# SCH_breakout_board_for_servo_2022-09-03.net
KiCad netlist of a schematic drawn in EasyEDA
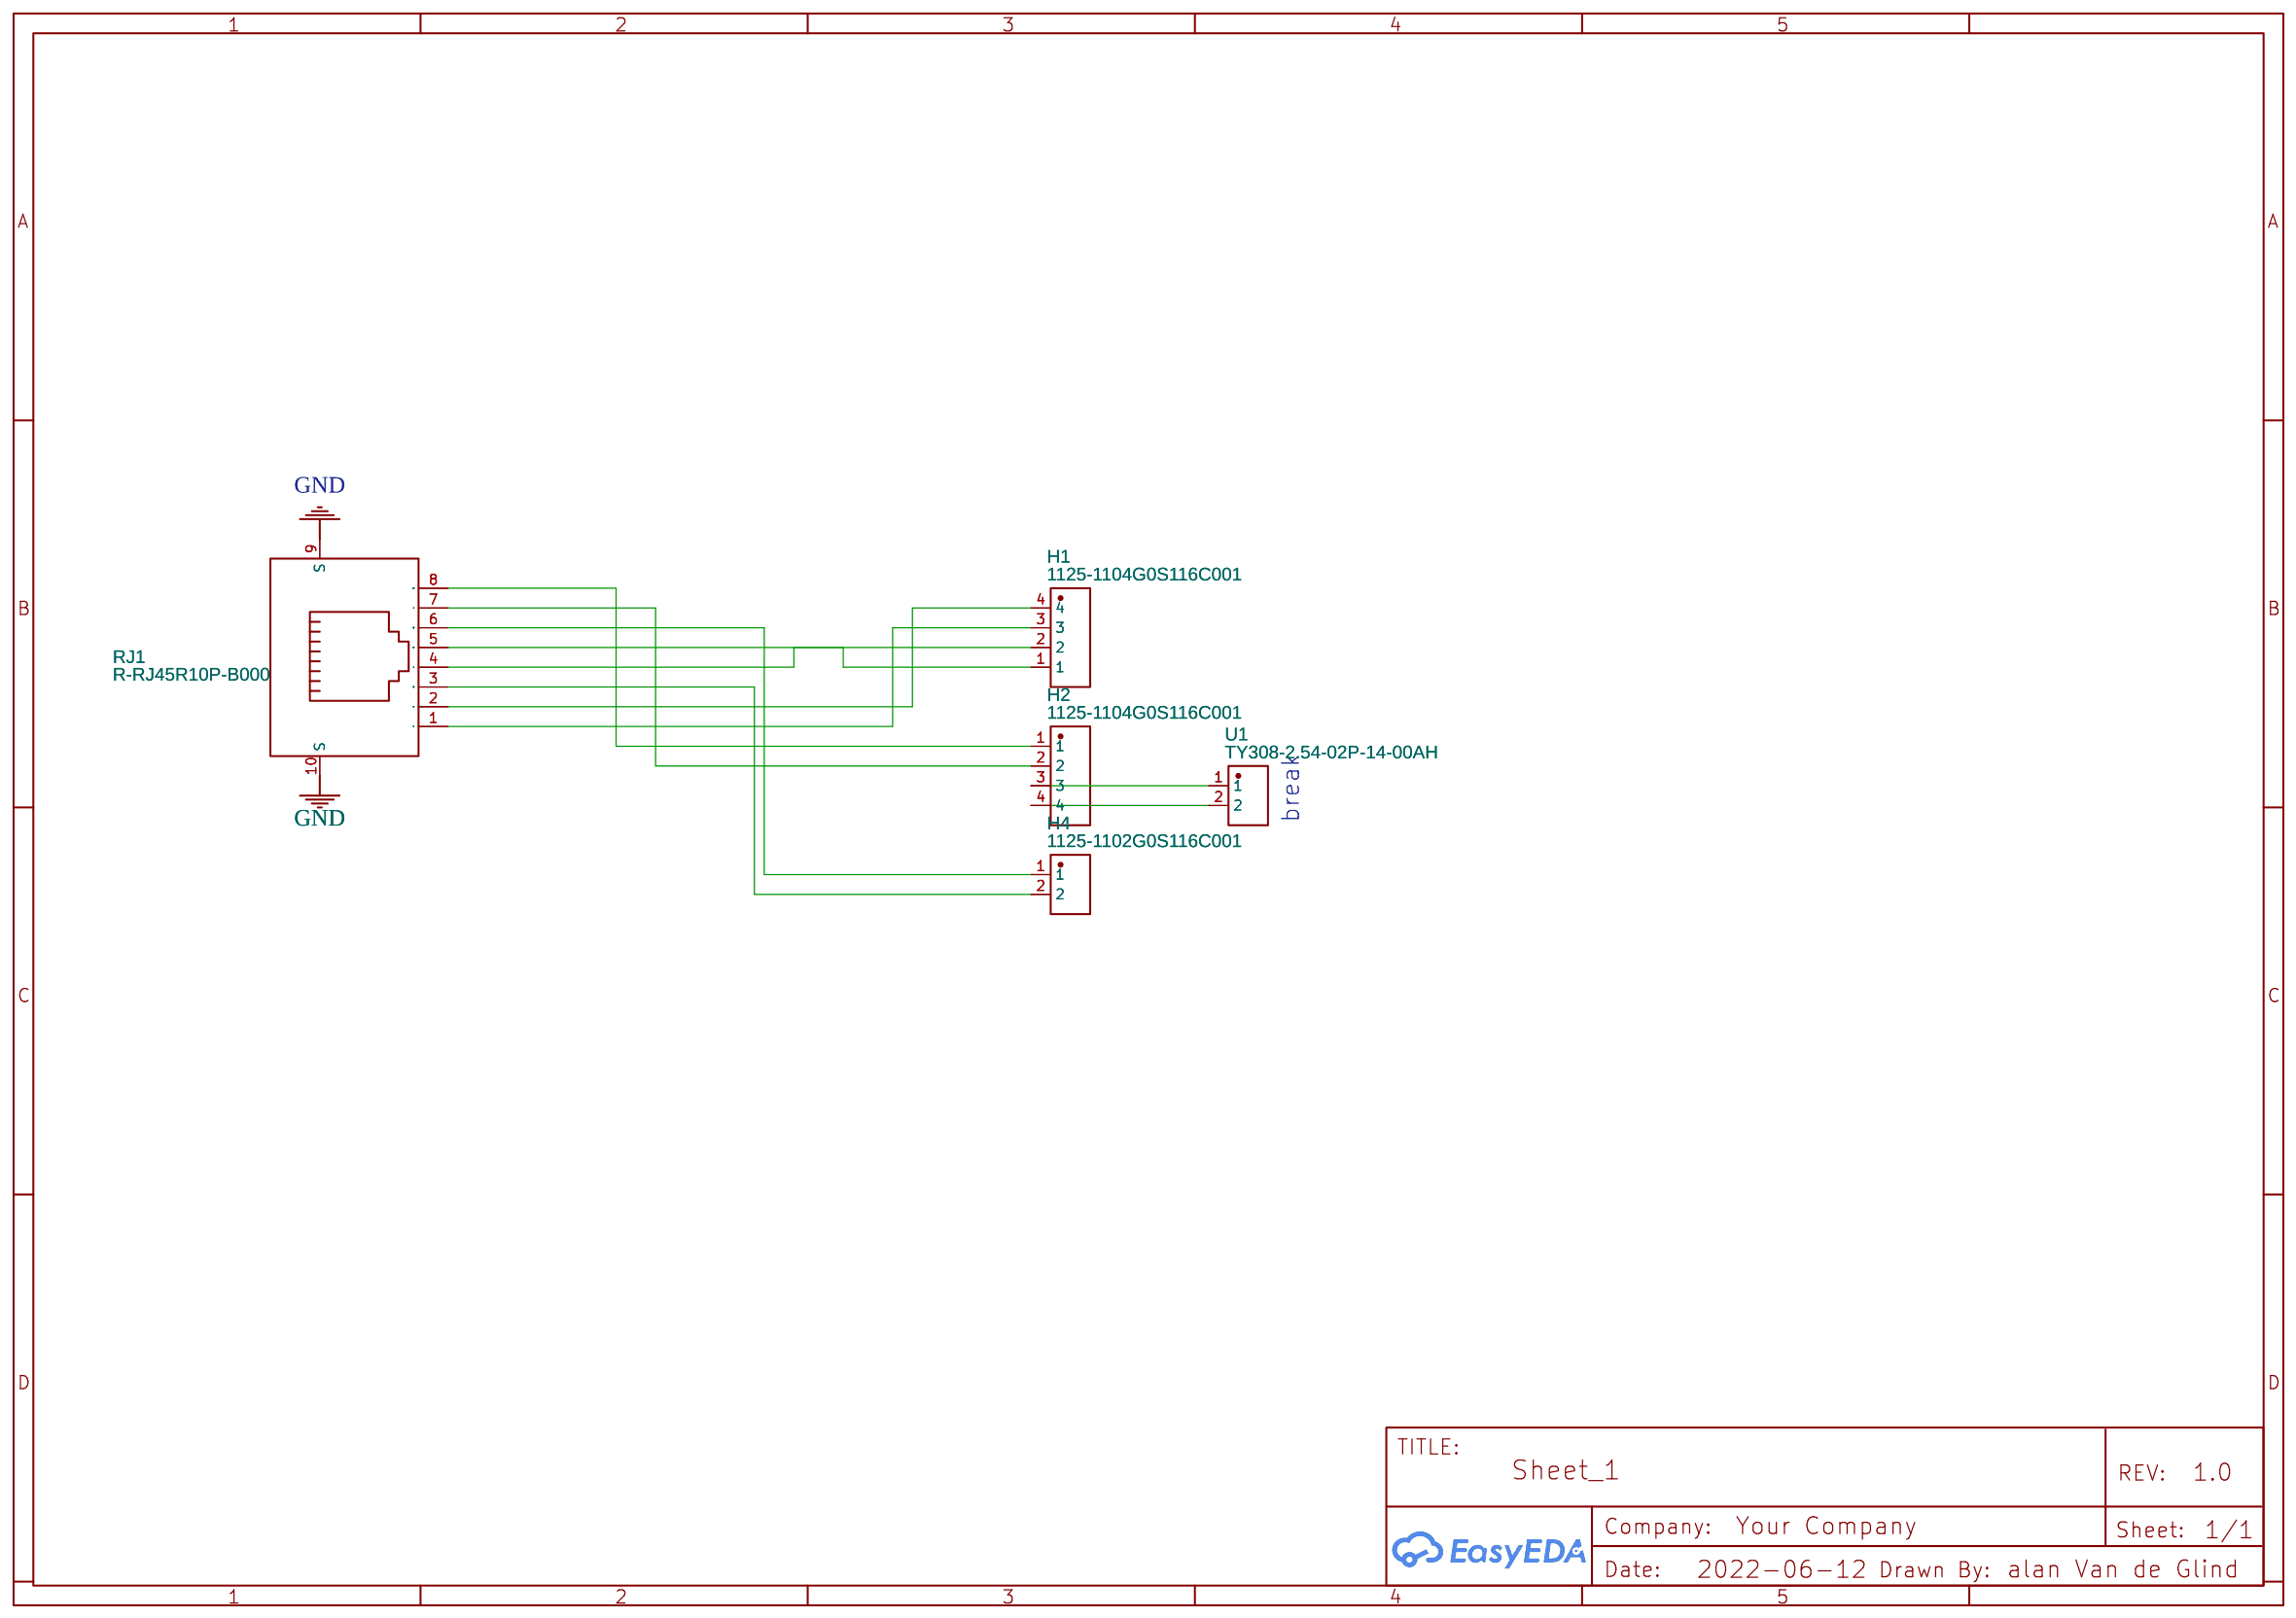
[diagram p0: schematic sheet]

(export (version "E")
  (design (tool "Eeschema 10.0.6"))
  (components
    (comp (ref "H1")
      (value "1125-1104G0S116C001")
      (fields (field (name "BOM_Supplier Part") "C920779"))
      (libsource (lib "") (part "1125-1104G0S116C001_1"))
    )
    (comp (ref "H2")
      (value "1125-1104G0S116C001")
      (fields (field (name "BOM_Supplier Part") "C920779"))
      (libsource (lib "") (part "1125-1104G0S116C001"))
    )
    (comp (ref "H4")
      (value "1125-1102G0S116C001")
      (fields (field (name "BOM_Supplier Part") "C920781"))
      (libsource (lib "") (part "1125-1102G0S116C001"))
    )
    (comp (ref "RJ1")
      (value "R-RJ45R10P-B000")
      (fields (field (name "BOM_Supplier Part") "C386758"))
      (libsource (lib "") (part "R-RJ45R10P-B000"))
    )
    (comp (ref "U1")
      (value "TY308-2.54-02P-14-00AH")
      (fields (field (name "BOM_Supplier Part") "C2840316"))
      (libsource (lib "") (part "TY308-2.54-02P-14-00AH"))
    )
  )
  (nets
    (net (code "1") (name "GND") (class "Default")
      (node (ref "RJ1") (pin "10") (pinfunction "S_10") (pintype "unspecified"))
      (node (ref "RJ1") (pin "9") (pinfunction "S_9") (pintype "unspecified"))
    )
    (net (code "2") (name "Net-(H1-Pad1)") (class "Default")
      (node (ref "H1") (pin "1") (pinfunction "1_1") (pintype "unspecified"))
      (node (ref "RJ1") (pin "5") (pinfunction "5_5") (pintype "unspecified"))
    )
    (net (code "3") (name "Net-(H1-Pad2)") (class "Default")
      (node (ref "H1") (pin "2") (pinfunction "2_2") (pintype "unspecified"))
      (node (ref "RJ1") (pin "4") (pinfunction "4_4") (pintype "unspecified"))
    )
    (net (code "4") (name "Net-(H1-Pad3)") (class "Default")
      (node (ref "H1") (pin "3") (pinfunction "3_3") (pintype "unspecified"))
      (node (ref "RJ1") (pin "1") (pinfunction "1_1") (pintype "unspecified"))
    )
    (net (code "5") (name "Net-(H1-Pad4)") (class "Default")
      (node (ref "H1") (pin "4") (pinfunction "4_4") (pintype "unspecified"))
      (node (ref "RJ1") (pin "2") (pinfunction "2_2") (pintype "unspecified"))
    )
    (net (code "6") (name "Net-(H2-Pad1)") (class "Default")
      (node (ref "H2") (pin "1") (pinfunction "1_1") (pintype "unspecified"))
      (node (ref "RJ1") (pin "8") (pinfunction "8_8") (pintype "unspecified"))
    )
    (net (code "7") (name "Net-(H2-Pad2)") (class "Default")
      (node (ref "H2") (pin "2") (pinfunction "2_2") (pintype "unspecified"))
      (node (ref "RJ1") (pin "7") (pinfunction "7_7") (pintype "unspecified"))
    )
    (net (code "8") (name "Net-(H2-Pad3)") (class "Default")
      (node (ref "H2") (pin "3") (pinfunction "3_3") (pintype "unspecified"))
      (node (ref "U1") (pin "1") (pinfunction "1_1") (pintype "unspecified"))
    )
    (net (code "9") (name "Net-(H2-Pad4)") (class "Default")
      (node (ref "H2") (pin "4") (pinfunction "4_4") (pintype "unspecified"))
      (node (ref "U1") (pin "2") (pinfunction "2_2") (pintype "unspecified"))
    )
    (net (code "10") (name "Net-(H4-Pad1)") (class "Default")
      (node (ref "H4") (pin "1") (pinfunction "1_1") (pintype "unspecified"))
      (node (ref "RJ1") (pin "6") (pinfunction "6_6") (pintype "unspecified"))
    )
    (net (code "11") (name "Net-(H4-Pad2)") (class "Default")
      (node (ref "H4") (pin "2") (pinfunction "2_2") (pintype "unspecified"))
      (node (ref "RJ1") (pin "3") (pinfunction "3_3") (pintype "unspecified"))
    )
  )
)
